# smartwatch.net
KiCad netlist of a schematic drawn in EAGLE
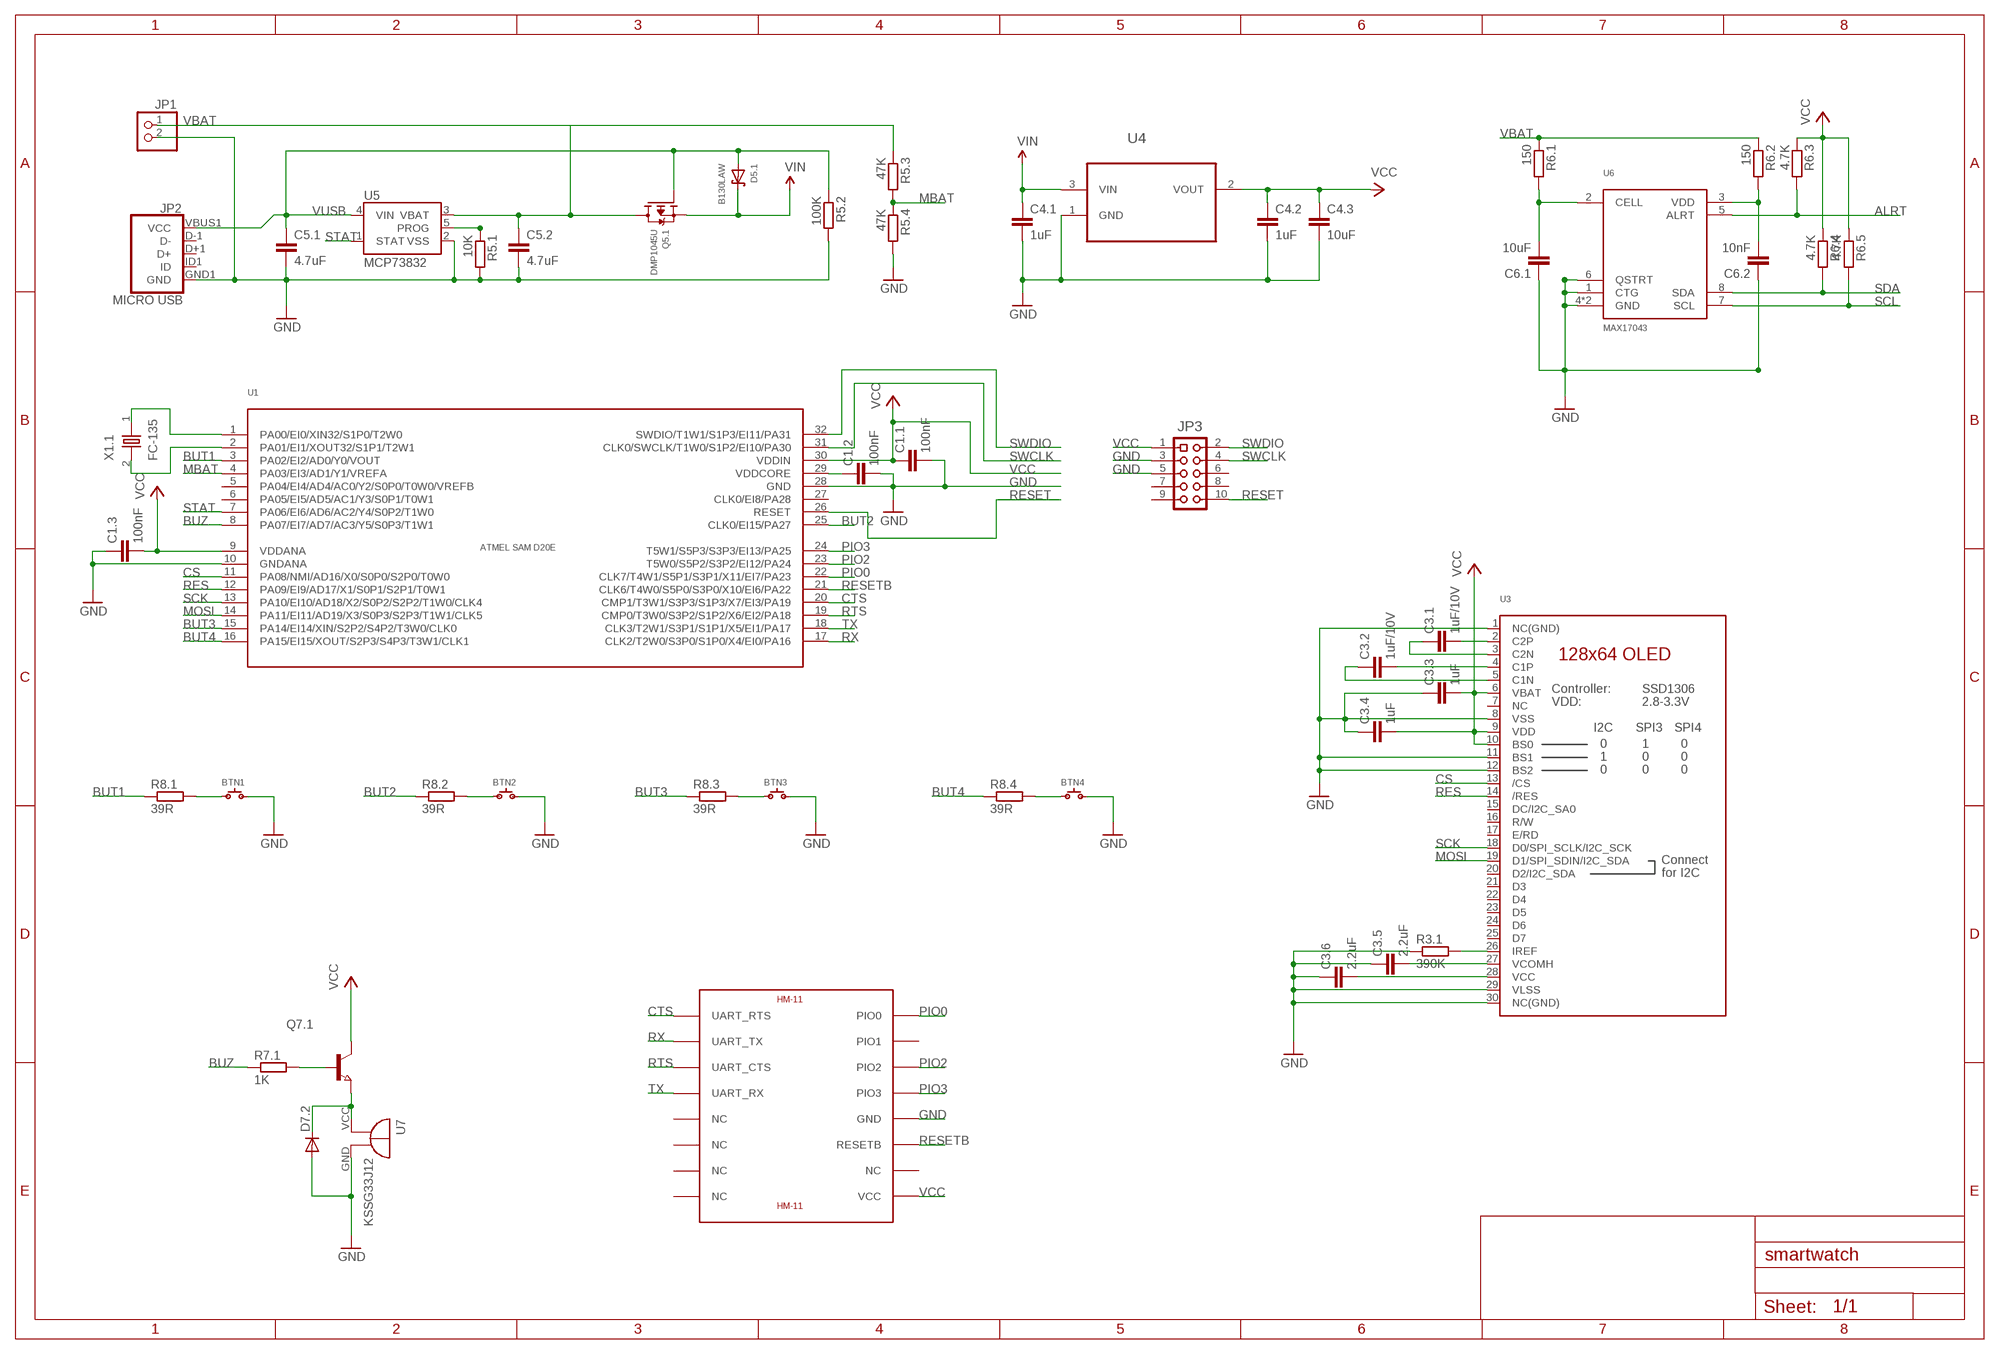
[diagram p0: schematic, sheet 1]

(export (version "E")
  (design (tool "Eeschema 10.0.6"))
  (components
    (comp (ref "BTN1")
      (value "SPST.B3U-3000P(M)")
      (footprint "eagle-import:B3U-3000P(M)")
      (libsource (lib "eagle-import") (part "SPST.B3U-3000P(M)"))
    )
    (comp (ref "BTN2")
      (value "SPST.B3U-3000P(M)")
      (footprint "eagle-import:B3U-3000P(M)")
      (libsource (lib "eagle-import") (part "SPST.B3U-3000P(M)"))
    )
    (comp (ref "BTN3")
      (value "SPST.B3U-3000P(M)")
      (footprint "eagle-import:B3U-3000P(M)")
      (libsource (lib "eagle-import") (part "SPST.B3U-3000P(M)"))
    )
    (comp (ref "BTN4")
      (value "SPST.B3U-3000P(M)")
      (footprint "eagle-import:B3U-3000P(M)")
      (libsource (lib "eagle-import") (part "SPST.B3U-3000P(M)"))
    )
    (comp (ref "C1.1")
      (value "100nF")
      (footprint "eagle-import:C0805")
      (libsource (lib "eagle-import") (part "C-EUC0805"))
    )
    (comp (ref "C1.2")
      (value "100nF")
      (footprint "eagle-import:C0805")
      (libsource (lib "eagle-import") (part "C-EUC0805"))
    )
    (comp (ref "C1.3")
      (value "100nF")
      (footprint "eagle-import:C0805")
      (libsource (lib "eagle-import") (part "C-EUC0805"))
    )
    (comp (ref "C3.1")
      (value "1uF/10V")
      (footprint "eagle-import:C0805")
      (libsource (lib "eagle-import") (part "C-EUC0805"))
    )
    (comp (ref "C3.2")
      (value "1uF/10V")
      (footprint "eagle-import:C0805")
      (libsource (lib "eagle-import") (part "C-EUC0805"))
    )
    (comp (ref "C3.3")
      (value "1uF")
      (footprint "eagle-import:C0805")
      (libsource (lib "eagle-import") (part "C-EUC0805"))
    )
    (comp (ref "C3.4")
      (value "1uF")
      (footprint "eagle-import:C0805")
      (libsource (lib "eagle-import") (part "C-EUC0805"))
    )
    (comp (ref "C3.5")
      (value "2.2uF")
      (footprint "eagle-import:C0805")
      (libsource (lib "eagle-import") (part "C-EUC0805"))
    )
    (comp (ref "C3.6")
      (value "2.2uF")
      (footprint "eagle-import:C0805")
      (libsource (lib "eagle-import") (part "C-EUC0805"))
    )
    (comp (ref "C4.1")
      (value "1uF")
      (footprint "eagle-import:C0805")
      (libsource (lib "eagle-import") (part "C-EUC0805"))
    )
    (comp (ref "C4.2")
      (value "1uF")
      (footprint "eagle-import:C0805")
      (libsource (lib "eagle-import") (part "C-EUC0805"))
    )
    (comp (ref "C4.3")
      (value "10uF")
      (footprint "eagle-import:C0805")
      (libsource (lib "eagle-import") (part "C-EUC0805"))
    )
    (comp (ref "C5.1")
      (value "4.7uF")
      (footprint "eagle-import:C0805")
      (libsource (lib "eagle-import") (part "C-EUC0805"))
    )
    (comp (ref "C5.2")
      (value "4.7uF")
      (footprint "eagle-import:C0805")
      (libsource (lib "eagle-import") (part "C-EUC0805"))
    )
    (comp (ref "C6.1")
      (value "10uF")
      (footprint "eagle-import:C0805")
      (libsource (lib "eagle-import") (part "C-EUC0805"))
    )
    (comp (ref "C6.2")
      (value "10nF")
      (footprint "eagle-import:C0805")
      (libsource (lib "eagle-import") (part "C-EUC0805"))
    )
    (comp (ref "D5.1")
      (value "B130LAW")
      (footprint "eagle-import:SOD-123")
      (libsource (lib "eagle-import") (part "DIODE-SCHOTTKYSOD-123"))
    )
    (comp (ref "D7.2")
      (value "CGRM4001-G")
      (footprint "eagle-import:SOD-123_MINI-SMA")
      (libsource (lib "eagle-import") (part "CGRM400-G1"))
    )
    (comp (ref "JP1")
      (value "PINHD-1X2")
      (footprint "eagle-import:1X02")
      (libsource (lib "eagle-import") (part "PINHD-1X2"))
    )
    (comp (ref "JP2")
      (value "MICRO USB")
      (footprint "eagle-import:USB-B-MICRO-SMD_V03")
      (libsource (lib "eagle-import") (part "USB_MICROB_PLUGCONN-11752"))
    )
    (comp (ref "JP3")
      (value "PF2X5SMD1.27MM")
      (footprint "eagle-import:PF2X5SMD50MIL")
      (libsource (lib "eagle-import") (part "PF2X5SMD1.27MM"))
    )
    (comp (ref "Q5.1")
      (value "DMP1045U")
      (footprint "eagle-import:SOT23-R")
      (libsource (lib "eagle-import") (part "MOSFET-P"))
    )
    (comp (ref "Q7.1")
      (value "NPN-TRANSISTOR_SOT23")
      (footprint "eagle-import:SOT23")
      (libsource (lib "eagle-import") (part "NPN-TRANSISTOR_SOT23"))
    )
    (comp (ref "R3.1")
      (value "390K")
      (footprint "eagle-import:R2012")
      (libsource (lib "eagle-import") (part "R-EU_R2012"))
    )
    (comp (ref "R5.1")
      (value "10K")
      (footprint "eagle-import:R2012")
      (libsource (lib "eagle-import") (part "R-EU_R2012"))
    )
    (comp (ref "R5.2")
      (value "100K")
      (footprint "eagle-import:R2012")
      (libsource (lib "eagle-import") (part "R-EU_R2012"))
    )
    (comp (ref "R5.3")
      (value "47K")
      (footprint "eagle-import:R2012")
      (libsource (lib "eagle-import") (part "R-EU_R2012"))
    )
    (comp (ref "R5.4")
      (value "47K")
      (footprint "eagle-import:R2012")
      (libsource (lib "eagle-import") (part "R-EU_R2012"))
    )
    (comp (ref "R6.1")
      (value "150")
      (footprint "eagle-import:R2012")
      (libsource (lib "eagle-import") (part "R-EU_R2012"))
    )
    (comp (ref "R6.2")
      (value "150")
      (footprint "eagle-import:R2012")
      (libsource (lib "eagle-import") (part "R-EU_R2012"))
    )
    (comp (ref "R6.3")
      (value "4.7K")
      (footprint "eagle-import:R2012")
      (libsource (lib "eagle-import") (part "R-EU_R2012"))
    )
    (comp (ref "R6.4")
      (value "4.7K")
      (footprint "eagle-import:R2012")
      (libsource (lib "eagle-import") (part "R-EU_R2012"))
    )
    (comp (ref "R6.5")
      (value "4.7K")
      (footprint "eagle-import:R2012")
      (libsource (lib "eagle-import") (part "R-EU_R2012"))
    )
    (comp (ref "R7.1")
      (value "1K")
      (footprint "eagle-import:R2012")
      (libsource (lib "eagle-import") (part "R-EU_R2012"))
    )
    (comp (ref "R8.1")
      (value "39R")
      (footprint "eagle-import:R2012")
      (libsource (lib "eagle-import") (part "R-EU_R2012"))
    )
    (comp (ref "R8.2")
      (value "39R")
      (footprint "eagle-import:R2012")
      (libsource (lib "eagle-import") (part "R-EU_R2012"))
    )
    (comp (ref "R8.3")
      (value "39R")
      (footprint "eagle-import:R2012")
      (libsource (lib "eagle-import") (part "R-EU_R2012"))
    )
    (comp (ref "R8.4")
      (value "39R")
      (footprint "eagle-import:R2012")
      (libsource (lib "eagle-import") (part "R-EU_R2012"))
    )
    (comp (ref "U1")
      (value "SAMD20E")
      (footprint "eagle-import:TQFP32-08")
      (libsource (lib "eagle-import") (part "SAMD20E"))
    )
    (comp (ref "U2")
      (value "HM-11")
      (footprint "eagle-import:HM-11")
      (libsource (lib "eagle-import") (part "HM-11"))
    )
    (comp (ref "U3")
      (value "DISP_OLED_UG-2864HSWEG010.96\"")
      (footprint "eagle-import:UG-2864HSWEG01_0.96IN_WRAPAROUND")
      (libsource (lib "eagle-import") (part "DISP_OLED_UG-2864HSWEG010.96{dblquote}"))
    )
    (comp (ref "U4")
      (value "MCP1700T-3302E/TT")
      (footprint "eagle-import:SOT95P237X112-3N")
      (libsource (lib "eagle-import") (part "MCP1700T-3302E/TT"))
    )
    (comp (ref "U5")
      (value "MCP73832")
      (footprint "eagle-import:SOT23-5")
      (libsource (lib "eagle-import") (part "MCP73831"))
    )
    (comp (ref "U6")
      (value "MAX17043")
      (footprint "eagle-import:8-TDFN-EP")
      (libsource (lib "eagle-import") (part "MAX17043"))
    )
    (comp (ref "U7")
      (value "KSSG33J12")
      (footprint "eagle-import:KSSG33J12")
      (libsource (lib "eagle-import") (part "KSSG33J12"))
    )
    (comp (ref "X1.1")
      (value "FC-135")
      (footprint "eagle-import:FC-135")
      (libsource (lib "eagle-import") (part "FC-135FC-135"))
    )
  )
  (nets
    (net (code "1") (name "/ALRT") (class "Default")
      (node (ref "R6.3") (pin "2") (pinfunction "2_2") (pintype "passive"))
      (node (ref "U6") (pin "5") (pinfunction "ALRT_5") (pintype "bidirectional"))
    )
    (net (code "2") (name "/BUT1") (class "Default")
      (node (ref "R8.1") (pin "1") (pinfunction "1_1") (pintype "passive"))
      (node (ref "U1") (pin "3") (pinfunction "PA02/EI2/AD0/Y0/VOUT_3") (pintype "bidirectional"))
    )
    (net (code "3") (name "/BUT2") (class "Default")
      (node (ref "R8.2") (pin "1") (pinfunction "1_1") (pintype "passive"))
      (node (ref "U1") (pin "25") (pinfunction "CLK0/EI15/PA27_25") (pintype "bidirectional"))
    )
    (net (code "4") (name "/BUT3") (class "Default")
      (node (ref "R8.3") (pin "1") (pinfunction "1_1") (pintype "passive"))
      (node (ref "U1") (pin "15") (pinfunction "PA14/EI14/XIN/S2P2/S4P2/T3W0/CLK0_15") (pintype "bidirectional"))
    )
    (net (code "5") (name "/BUT4") (class "Default")
      (node (ref "R8.4") (pin "1") (pinfunction "1_1") (pintype "passive"))
      (node (ref "U1") (pin "16") (pinfunction "PA15/EI15/XOUT/S2P3/S4P3/T3W1/CLK1_16") (pintype "bidirectional"))
    )
    (net (code "6") (name "/BUZ") (class "Default")
      (node (ref "R7.1") (pin "1") (pinfunction "1_1") (pintype "passive"))
      (node (ref "U1") (pin "8") (pinfunction "PA07/EI7/AD7/AC3/Y5/S0P3/T1W1_8") (pintype "bidirectional"))
    )
    (net (code "7") (name "/CS") (class "Default")
      (node (ref "U1") (pin "11") (pinfunction "PA08/NMI/AD16/X0/S0P0/S2P0/T0W0_11") (pintype "bidirectional"))
      (node (ref "U3") (pin "13") (pinfunction "/CS_13") (pintype "input"))
    )
    (net (code "8") (name "/CTS") (class "Default")
      (node (ref "U1") (pin "20") (pinfunction "CMP1/T3W1/S3P3/S1P3/X7/EI3/PA19_20") (pintype "bidirectional"))
      (node (ref "U2") (pin "UART_RTS") (pinfunction "UART_RTS_UART_RTS") (pintype "bidirectional"))
    )
    (net (code "9") (name "/MBAT") (class "Default")
      (node (ref "R5.3") (pin "2") (pinfunction "2_2") (pintype "passive"))
      (node (ref "R5.4") (pin "1") (pinfunction "1_1") (pintype "passive"))
      (node (ref "U1") (pin "4") (pinfunction "PA03/EI3/AD1/Y1/VREFA_4") (pintype "bidirectional"))
    )
    (net (code "10") (name "/MOSI") (class "Default")
      (node (ref "U1") (pin "14") (pinfunction "PA11/EI11/AD19/X3/S0P3/S2P3/T1W1/CLK5_14") (pintype "bidirectional"))
      (node (ref "U3") (pin "19") (pinfunction "D1/SPI_SDIN/I2C_SDA_19") (pintype "bidirectional"))
    )
    (net (code "11") (name "/PIO0") (class "Default")
      (node (ref "U1") (pin "22") (pinfunction "CLK7/T4W1/S5P1/S3P1/X11/EI7/PA23_22") (pintype "bidirectional"))
      (node (ref "U2") (pin "PIO0") (pinfunction "PIO0_PIO0") (pintype "bidirectional"))
    )
    (net (code "12") (name "/PIO2") (class "Default")
      (node (ref "U1") (pin "23") (pinfunction "T5W0/S5P2/S3P2/EI12/PA24_23") (pintype "bidirectional"))
      (node (ref "U2") (pin "PIO2") (pinfunction "PIO2_PIO2") (pintype "bidirectional"))
    )
    (net (code "13") (name "/PIO3") (class "Default")
      (node (ref "U1") (pin "24") (pinfunction "T5W1/S5P3/S3P3/EI13/PA25_24") (pintype "bidirectional"))
      (node (ref "U2") (pin "PIO3") (pinfunction "PIO3_PIO3") (pintype "bidirectional"))
    )
    (net (code "14") (name "/RES") (class "Default")
      (node (ref "U1") (pin "12") (pinfunction "PA09/EI9/AD17/X1/S0P1/S2P1/T0W1_12") (pintype "bidirectional"))
      (node (ref "U3") (pin "14") (pinfunction "/RES_14") (pintype "input"))
    )
    (net (code "15") (name "/RESET") (class "Default")
      (node (ref "JP3") (pin "10") (pinfunction "10_10") (pintype "passive"))
      (node (ref "U1") (pin "26") (pinfunction "RESET_26") (pintype "bidirectional"))
    )
    (net (code "16") (name "/RESETB") (class "Default")
      (node (ref "U1") (pin "21") (pinfunction "CLK6/T4W0/S5P0/S3P0/X10/EI6/PA22_21") (pintype "bidirectional"))
      (node (ref "U2") (pin "RESETB") (pinfunction "RESETB_RESETB") (pintype "bidirectional"))
    )
    (net (code "17") (name "/RTS") (class "Default")
      (node (ref "U1") (pin "19") (pinfunction "CMP0/T3W0/S3P2/S1P2/X6/EI2/PA18_19") (pintype "bidirectional"))
      (node (ref "U2") (pin "UART_CTS") (pinfunction "UART_CTS_UART_CTS") (pintype "bidirectional"))
    )
    (net (code "18") (name "/RX") (class "Default")
      (node (ref "U1") (pin "17") (pinfunction "CLK2/T2W0/S3P0/S1P0/X4/EI0/PA16_17") (pintype "bidirectional"))
      (node (ref "U2") (pin "UART_TX") (pinfunction "UART_TX_UART_TX") (pintype "bidirectional"))
    )
    (net (code "19") (name "/SCK") (class "Default")
      (node (ref "U1") (pin "13") (pinfunction "PA10/EI10/AD18/X2/S0P2/S2P2/T1W0/CLK4_13") (pintype "bidirectional"))
      (node (ref "U3") (pin "18") (pinfunction "D0/SPI_SCLK/I2C_SCK_18") (pintype "bidirectional"))
    )
    (net (code "20") (name "/SCL") (class "Default")
      (node (ref "R6.5") (pin "2") (pinfunction "2_2") (pintype "passive"))
      (node (ref "U6") (pin "7") (pinfunction "SCL_7") (pintype "bidirectional"))
    )
    (net (code "21") (name "/SDA") (class "Default")
      (node (ref "R6.4") (pin "2") (pinfunction "2_2") (pintype "passive"))
      (node (ref "U6") (pin "8") (pinfunction "SDA_8") (pintype "bidirectional"))
    )
    (net (code "22") (name "/STAT") (class "Default")
      (node (ref "U1") (pin "7") (pinfunction "PA06/EI6/AD6/AC2/Y4/S0P2/T1W0_7") (pintype "bidirectional"))
      (node (ref "U5") (pin "1") (pinfunction "STAT_1") (pintype "output"))
    )
    (net (code "23") (name "/SWCLK") (class "Default")
      (node (ref "JP3") (pin "4") (pinfunction "4_4") (pintype "passive"))
      (node (ref "U1") (pin "31") (pinfunction "CLK0/SWCLK/T1W0/S1P2/EI10/PA30_31") (pintype "bidirectional"))
    )
    (net (code "24") (name "/SWDIO") (class "Default")
      (node (ref "JP3") (pin "2") (pinfunction "2_2") (pintype "passive"))
      (node (ref "U1") (pin "32") (pinfunction "SWDIO/T1W1/S1P3/EI11/PA31_32") (pintype "bidirectional"))
    )
    (net (code "25") (name "/TX") (class "Default")
      (node (ref "U1") (pin "18") (pinfunction "CLK3/T2W1/S3P1/S1P1/X5/EI1/PA17_18") (pintype "bidirectional"))
      (node (ref "U2") (pin "UART_RX") (pinfunction "UART_RX_UART_RX") (pintype "bidirectional"))
    )
    (net (code "26") (name "/VBAT") (class "Default")
      (node (ref "C5.2") (pin "1") (pinfunction "1_1") (pintype "passive"))
      (node (ref "JP1") (pin "1") (pinfunction "1_1") (pintype "passive"))
      (node (ref "Q5.1") (pin "3") (pinfunction "D_3") (pintype "passive"))
      (node (ref "R5.3") (pin "1") (pinfunction "1_1") (pintype "passive"))
      (node (ref "R6.1") (pin "1") (pinfunction "1_1") (pintype "passive"))
      (node (ref "R6.2") (pin "1") (pinfunction "1_1") (pintype "passive"))
      (node (ref "U5") (pin "3") (pinfunction "VBAT_3") (pintype "power_in"))
    )
    (net (code "27") (name "/VUSB") (class "Default")
      (node (ref "C5.1") (pin "1") (pinfunction "1_1") (pintype "passive"))
      (node (ref "D5.1") (pin "A") (pinfunction "A_A") (pintype "passive"))
      (node (ref "JP2") (pin "VBUS1") (pinfunction "VCC_VBUS1") (pintype "bidirectional"))
      (node (ref "Q5.1") (pin "1") (pinfunction "G_1") (pintype "passive"))
      (node (ref "R5.2") (pin "1") (pinfunction "1_1") (pintype "passive"))
      (node (ref "U5") (pin "4") (pinfunction "VIN_4") (pintype "power_in"))
    )
    (net (code "28") (name "GND") (class "Default")
      (node (ref "BTN1") (pin "2") (pinfunction "2_2") (pintype "bidirectional"))
      (node (ref "BTN2") (pin "2") (pinfunction "2_2") (pintype "bidirectional"))
      (node (ref "BTN3") (pin "2") (pinfunction "2_2") (pintype "bidirectional"))
      (node (ref "BTN4") (pin "2") (pinfunction "2_2") (pintype "bidirectional"))
      (node (ref "C1.1") (pin "2") (pinfunction "2_2") (pintype "passive"))
      (node (ref "C1.2") (pin "2") (pinfunction "2_2") (pintype "passive"))
      (node (ref "C1.3") (pin "1") (pinfunction "1_1") (pintype "passive"))
      (node (ref "C3.3") (pin "1") (pinfunction "1_1") (pintype "passive"))
      (node (ref "C3.4") (pin "1") (pinfunction "1_1") (pintype "passive"))
      (node (ref "C3.5") (pin "1") (pinfunction "1_1") (pintype "passive"))
      (node (ref "C3.6") (pin "1") (pinfunction "1_1") (pintype "passive"))
      (node (ref "C4.1") (pin "2") (pinfunction "2_2") (pintype "passive"))
      (node (ref "C4.2") (pin "2") (pinfunction "2_2") (pintype "passive"))
      (node (ref "C4.3") (pin "2") (pinfunction "2_2") (pintype "passive"))
      (node (ref "C5.1") (pin "2") (pinfunction "2_2") (pintype "passive"))
      (node (ref "C5.2") (pin "2") (pinfunction "2_2") (pintype "passive"))
      (node (ref "C6.1") (pin "1") (pinfunction "1_1") (pintype "passive"))
      (node (ref "C6.2") (pin "1") (pinfunction "1_1") (pintype "passive"))
      (node (ref "D7.2") (pin "A") (pinfunction "A_A") (pintype "passive"))
      (node (ref "JP1") (pin "2") (pinfunction "2_2") (pintype "passive"))
      (node (ref "JP2") (pin "GND1") (pinfunction "GND_GND1") (pintype "bidirectional"))
      (node (ref "JP3") (pin "3") (pinfunction "3_3") (pintype "passive"))
      (node (ref "JP3") (pin "5") (pinfunction "5_5") (pintype "passive"))
      (node (ref "R3.1") (pin "1") (pinfunction "1_1") (pintype "passive"))
      (node (ref "R5.1") (pin "2") (pinfunction "2_2") (pintype "passive"))
      (node (ref "R5.2") (pin "2") (pinfunction "2_2") (pintype "passive"))
      (node (ref "R5.4") (pin "2") (pinfunction "2_2") (pintype "passive"))
      (node (ref "U1") (pin "10") (pinfunction "GNDANA_10") (pintype "bidirectional"))
      (node (ref "U1") (pin "28") (pinfunction "GND_28") (pintype "bidirectional"))
      (node (ref "U2") (pin "GND") (pinfunction "GND_GND") (pintype "bidirectional"))
      (node (ref "U3") (pin "1") (pinfunction "NC(GND)_1") (pintype "input"))
      (node (ref "U3") (pin "11") (pinfunction "BS1_11") (pintype "input"))
      (node (ref "U3") (pin "12") (pinfunction "BS2_12") (pintype "input"))
      (node (ref "U3") (pin "29") (pinfunction "VLSS_29") (pintype "power_in"))
      (node (ref "U3") (pin "30") (pinfunction "NC(GND)_30") (pintype "input"))
      (node (ref "U3") (pin "8") (pinfunction "VSS_8") (pintype "power_in"))
      (node (ref "U4") (pin "1") (pinfunction "GND_1") (pintype "passive"))
      (node (ref "U5") (pin "2") (pinfunction "VSS_2") (pintype "power_in"))
      (node (ref "U6") (pin "1") (pinfunction "CTG_1") (pintype "bidirectional"))
      (node (ref "U6") (pin "4") (pinfunction "GND_4") (pintype "bidirectional"))
      (node (ref "U6") (pin "6") (pinfunction "QSTRT_6") (pintype "bidirectional"))
      (node (ref "U6") (pin "9") (pinfunction "GND_9") (pintype "bidirectional"))
      (node (ref "U7") (pin "GND") (pinfunction "-_GND") (pintype "passive"))
    )
    (net (code "29") (name "Net-(BTN1-Pad1)") (class "Default")
      (node (ref "BTN1") (pin "1") (pinfunction "1_1") (pintype "bidirectional"))
      (node (ref "R8.1") (pin "2") (pinfunction "2_2") (pintype "passive"))
    )
    (net (code "30") (name "Net-(BTN2-Pad1)") (class "Default")
      (node (ref "BTN2") (pin "1") (pinfunction "1_1") (pintype "bidirectional"))
      (node (ref "R8.2") (pin "2") (pinfunction "2_2") (pintype "passive"))
    )
    (net (code "31") (name "Net-(BTN3-Pad1)") (class "Default")
      (node (ref "BTN3") (pin "1") (pinfunction "1_1") (pintype "bidirectional"))
      (node (ref "R8.3") (pin "2") (pinfunction "2_2") (pintype "passive"))
    )
    (net (code "32") (name "Net-(BTN4-Pad1)") (class "Default")
      (node (ref "BTN4") (pin "1") (pinfunction "1_1") (pintype "bidirectional"))
      (node (ref "R8.4") (pin "2") (pinfunction "2_2") (pintype "passive"))
    )
    (net (code "33") (name "Net-(Q7.1-B)") (class "Default")
      (node (ref "Q7.1") (pin "1") (pinfunction "B_1") (pintype "passive"))
      (node (ref "R7.1") (pin "2") (pinfunction "2_2") (pintype "passive"))
    )
    (net (code "34") (name "Net-(Q7.1-E)") (class "Default")
      (node (ref "D7.2") (pin "C") (pinfunction "C_C") (pintype "passive"))
      (node (ref "Q7.1") (pin "2") (pinfunction "E_2") (pintype "passive"))
      (node (ref "U7") (pin "VCC") (pinfunction "+_VCC") (pintype "passive"))
    )
    (net (code "35") (name "Net-(U1-PA00{slash}EI0{slash}XIN32{slash}S1P0{slash}T2W0)") (class "Default")
      (node (ref "U1") (pin "1") (pinfunction "PA00/EI0/XIN32/S1P0/T2W0_1") (pintype "bidirectional"))
      (node (ref "X1.1") (pin "1") (pinfunction "1_1") (pintype "passive"))
    )
    (net (code "36") (name "Net-(U1-PA01{slash}EI1{slash}XOUT32{slash}S1P1{slash}T2W1)") (class "Default")
      (node (ref "U1") (pin "2") (pinfunction "PA01/EI1/XOUT32/S1P1/T2W1_2") (pintype "bidirectional"))
      (node (ref "X1.1") (pin "2") (pinfunction "2_2") (pintype "passive"))
    )
    (net (code "37") (name "Net-(U1-VDDCORE)") (class "Default")
      (node (ref "C1.2") (pin "1") (pinfunction "1_1") (pintype "passive"))
      (node (ref "U1") (pin "29") (pinfunction "VDDCORE_29") (pintype "bidirectional"))
    )
    (net (code "38") (name "Net-(U3-C1N)") (class "Default")
      (node (ref "C3.2") (pin "1") (pinfunction "1_1") (pintype "passive"))
      (node (ref "U3") (pin "5") (pinfunction "C1N_5") (pintype "input"))
    )
    (net (code "39") (name "Net-(U3-C1P)") (class "Default")
      (node (ref "C3.2") (pin "2") (pinfunction "2_2") (pintype "passive"))
      (node (ref "U3") (pin "4") (pinfunction "C1P_4") (pintype "input"))
    )
    (net (code "40") (name "Net-(U3-C2N)") (class "Default")
      (node (ref "C3.1") (pin "1") (pinfunction "1_1") (pintype "passive"))
      (node (ref "U3") (pin "3") (pinfunction "C2N_3") (pintype "input"))
    )
    (net (code "41") (name "Net-(U3-C2P)") (class "Default")
      (node (ref "C3.1") (pin "2") (pinfunction "2_2") (pintype "passive"))
      (node (ref "U3") (pin "2") (pinfunction "C2P_2") (pintype "input"))
    )
    (net (code "42") (name "Net-(U3-IREF)") (class "Default")
      (node (ref "R3.1") (pin "2") (pinfunction "2_2") (pintype "passive"))
      (node (ref "U3") (pin "26") (pinfunction "IREF_26") (pintype "input"))
    )
    (net (code "43") (name "Net-(U3-VCC)") (class "Default")
      (node (ref "C3.6") (pin "2") (pinfunction "2_2") (pintype "passive"))
      (node (ref "U3") (pin "28") (pinfunction "VCC_28") (pintype "power_in"))
    )
    (net (code "44") (name "Net-(U3-VCOMH)") (class "Default")
      (node (ref "C3.5") (pin "2") (pinfunction "2_2") (pintype "passive"))
      (node (ref "U3") (pin "27") (pinfunction "VCOMH_27") (pintype "output"))
    )
    (net (code "45") (name "Net-(U5-PROG)") (class "Default")
      (node (ref "R5.1") (pin "1") (pinfunction "1_1") (pintype "passive"))
      (node (ref "U5") (pin "5") (pinfunction "PROG_5") (pintype "input"))
    )
    (net (code "46") (name "Net-(U6-CELL)") (class "Default")
      (node (ref "C6.1") (pin "2") (pinfunction "2_2") (pintype "passive"))
      (node (ref "R6.1") (pin "2") (pinfunction "2_2") (pintype "passive"))
      (node (ref "U6") (pin "2") (pinfunction "CELL_2") (pintype "bidirectional"))
    )
    (net (code "47") (name "Net-(U6-VDD)") (class "Default")
      (node (ref "C6.2") (pin "2") (pinfunction "2_2") (pintype "passive"))
      (node (ref "R6.2") (pin "2") (pinfunction "2_2") (pintype "passive"))
      (node (ref "U6") (pin "3") (pinfunction "VDD_3") (pintype "bidirectional"))
    )
    (net (code "48") (name "VCC") (class "Default")
      (node (ref "C1.1") (pin "1") (pinfunction "1_1") (pintype "passive"))
      (node (ref "C1.3") (pin "2") (pinfunction "2_2") (pintype "passive"))
      (node (ref "C3.3") (pin "2") (pinfunction "2_2") (pintype "passive"))
      (node (ref "C3.4") (pin "2") (pinfunction "2_2") (pintype "passive"))
      (node (ref "C4.2") (pin "1") (pinfunction "1_1") (pintype "passive"))
      (node (ref "C4.3") (pin "1") (pinfunction "1_1") (pintype "passive"))
      (node (ref "JP3") (pin "1") (pinfunction "1_1") (pintype "passive"))
      (node (ref "Q7.1") (pin "3") (pinfunction "C_3") (pintype "passive"))
      (node (ref "R6.3") (pin "1") (pinfunction "1_1") (pintype "passive"))
      (node (ref "R6.4") (pin "1") (pinfunction "1_1") (pintype "passive"))
      (node (ref "R6.5") (pin "1") (pinfunction "1_1") (pintype "passive"))
      (node (ref "U1") (pin "30") (pinfunction "VDDIN_30") (pintype "bidirectional"))
      (node (ref "U1") (pin "9") (pinfunction "VDDANA_9") (pintype "bidirectional"))
      (node (ref "U2") (pin "VCC") (pinfunction "VCC_VCC") (pintype "bidirectional"))
      (node (ref "U3") (pin "10") (pinfunction "BS0_10") (pintype "input"))
      (node (ref "U3") (pin "6") (pinfunction "VBAT_6") (pintype "input"))
      (node (ref "U3") (pin "9") (pinfunction "VDD_9") (pintype "power_in"))
      (node (ref "U4") (pin "2") (pinfunction "VOUT_2") (pintype "output"))
    )
    (net (code "49") (name "VIN") (class "Default")
      (node (ref "C4.1") (pin "1") (pinfunction "1_1") (pintype "passive"))
      (node (ref "D5.1") (pin "C") (pinfunction "C_C") (pintype "passive"))
      (node (ref "Q5.1") (pin "2") (pinfunction "S_2") (pintype "passive"))
      (node (ref "U4") (pin "3") (pinfunction "VIN_3") (pintype "input"))
    )
    (net (code "50") (name "unconnected-(JP2-D+-PadD+1)") (class "Default")
      (node (ref "JP2") (pin "D+1") (pinfunction "D+_D+1") (pintype "bidirectional"))
    )
    (net (code "51") (name "unconnected-(JP2-D--PadD-1)") (class "Default")
      (node (ref "JP2") (pin "D-1") (pinfunction "D-_D-1") (pintype "bidirectional"))
    )
    (net (code "52") (name "unconnected-(JP2-ID-PadID1)") (class "Default")
      (node (ref "JP2") (pin "ID1") (pinfunction "ID_ID1") (pintype "bidirectional"))
    )
    (net (code "53") (name "unconnected-(JP3-Pad6)") (class "Default")
      (node (ref "JP3") (pin "6") (pinfunction "6_6") (pintype "passive"))
    )
    (net (code "54") (name "unconnected-(JP3-Pad7)") (class "Default")
      (node (ref "JP3") (pin "7") (pinfunction "7_7") (pintype "passive"))
    )
    (net (code "55") (name "unconnected-(JP3-Pad8)") (class "Default")
      (node (ref "JP3") (pin "8") (pinfunction "8_8") (pintype "passive"))
    )
    (net (code "56") (name "unconnected-(JP3-Pad9)") (class "Default")
      (node (ref "JP3") (pin "9") (pinfunction "9_9") (pintype "passive"))
    )
    (net (code "57") (name "unconnected-(U1-CLK0{slash}EI8{slash}PA28-Pad27)") (class "Default")
      (node (ref "U1") (pin "27") (pinfunction "CLK0/EI8/PA28_27") (pintype "bidirectional"))
    )
    (net (code "58") (name "unconnected-(U1-PA04{slash}EI4{slash}AD4{slash}AC0{slash}Y2{slash}S0P0{slash}T0W0{slash}VREFB-Pad5)") (class "Default")
      (node (ref "U1") (pin "5") (pinfunction "PA04/EI4/AD4/AC0/Y2/S0P0/T0W0/VREFB_5") (pintype "bidirectional"))
    )
    (net (code "59") (name "unconnected-(U1-PA05{slash}EI5{slash}AD5{slash}AC1{slash}Y3{slash}S0P1{slash}T0W1-Pad6)") (class "Default")
      (node (ref "U1") (pin "6") (pinfunction "PA05/EI5/AD5/AC1/Y3/S0P1/T0W1_6") (pintype "bidirectional"))
    )
    (net (code "60") (name "unconnected-(U2-NC-PadNC@5)") (class "Default")
      (node (ref "U2") (pin "NC@5") (pinfunction "NC_NC@5") (pintype "bidirectional"))
    )
    (net (code "61") (name "unconnected-(U2-NC-PadNC@6)") (class "Default")
      (node (ref "U2") (pin "NC@6") (pinfunction "NC_NC@6") (pintype "bidirectional"))
    )
    (net (code "62") (name "unconnected-(U2-NC-PadNC@7)") (class "Default")
      (node (ref "U2") (pin "NC@7") (pinfunction "NC_NC@7") (pintype "bidirectional"))
    )
    (net (code "63") (name "unconnected-(U2-NC-PadNC@8)") (class "Default")
      (node (ref "U2") (pin "NC@8") (pinfunction "NC_NC@8") (pintype "bidirectional"))
    )
    (net (code "64") (name "unconnected-(U2-NC-PadNC@10)") (class "Default")
      (node (ref "U2") (pin "NC@10") (pinfunction "NC_NC@10") (pintype "bidirectional"))
    )
    (net (code "65") (name "unconnected-(U2-PadPIO1)") (class "Default")
      (node (ref "U2") (pin "PIO1") (pinfunction "PIO1_PIO1") (pintype "bidirectional"))
    )
    (net (code "66") (name "unconnected-(U3-D2{slash}I2C_SDA-Pad20)") (class "Default")
      (node (ref "U3") (pin "20") (pinfunction "D2/I2C_SDA_20") (pintype "bidirectional"))
    )
    (net (code "67") (name "unconnected-(U3-D3-Pad21)") (class "Default")
      (node (ref "U3") (pin "21") (pinfunction "D3_21") (pintype "bidirectional"))
    )
    (net (code "68") (name "unconnected-(U3-D4-Pad22)") (class "Default")
      (node (ref "U3") (pin "22") (pinfunction "D4_22") (pintype "bidirectional"))
    )
    (net (code "69") (name "unconnected-(U3-D5-Pad23)") (class "Default")
      (node (ref "U3") (pin "23") (pinfunction "D5_23") (pintype "bidirectional"))
    )
    (net (code "70") (name "unconnected-(U3-D6-Pad24)") (class "Default")
      (node (ref "U3") (pin "24") (pinfunction "D6_24") (pintype "bidirectional"))
    )
    (net (code "71") (name "unconnected-(U3-D7-Pad25)") (class "Default")
      (node (ref "U3") (pin "25") (pinfunction "D7_25") (pintype "bidirectional"))
    )
    (net (code "72") (name "unconnected-(U3-DC{slash}I2C_SA0-Pad15)") (class "Default")
      (node (ref "U3") (pin "15") (pinfunction "DC/I2C_SA0_15") (pintype "input"))
    )
    (net (code "73") (name "unconnected-(U3-E{slash}RD-Pad17)") (class "Default")
      (node (ref "U3") (pin "17") (pinfunction "E/RD_17") (pintype "input"))
    )
    (net (code "74") (name "unconnected-(U3-NC-Pad7)") (class "Default")
      (node (ref "U3") (pin "7") (pinfunction "NC_7") (pintype "no_connect"))
    )
    (net (code "75") (name "unconnected-(U3-R{slash}W-Pad16)") (class "Default")
      (node (ref "U3") (pin "16") (pinfunction "R/W_16") (pintype "input"))
    )
  )
)
